# wagband_chestpiece_pre_route.net
KiCad netlist of a schematic drawn in EAGLE
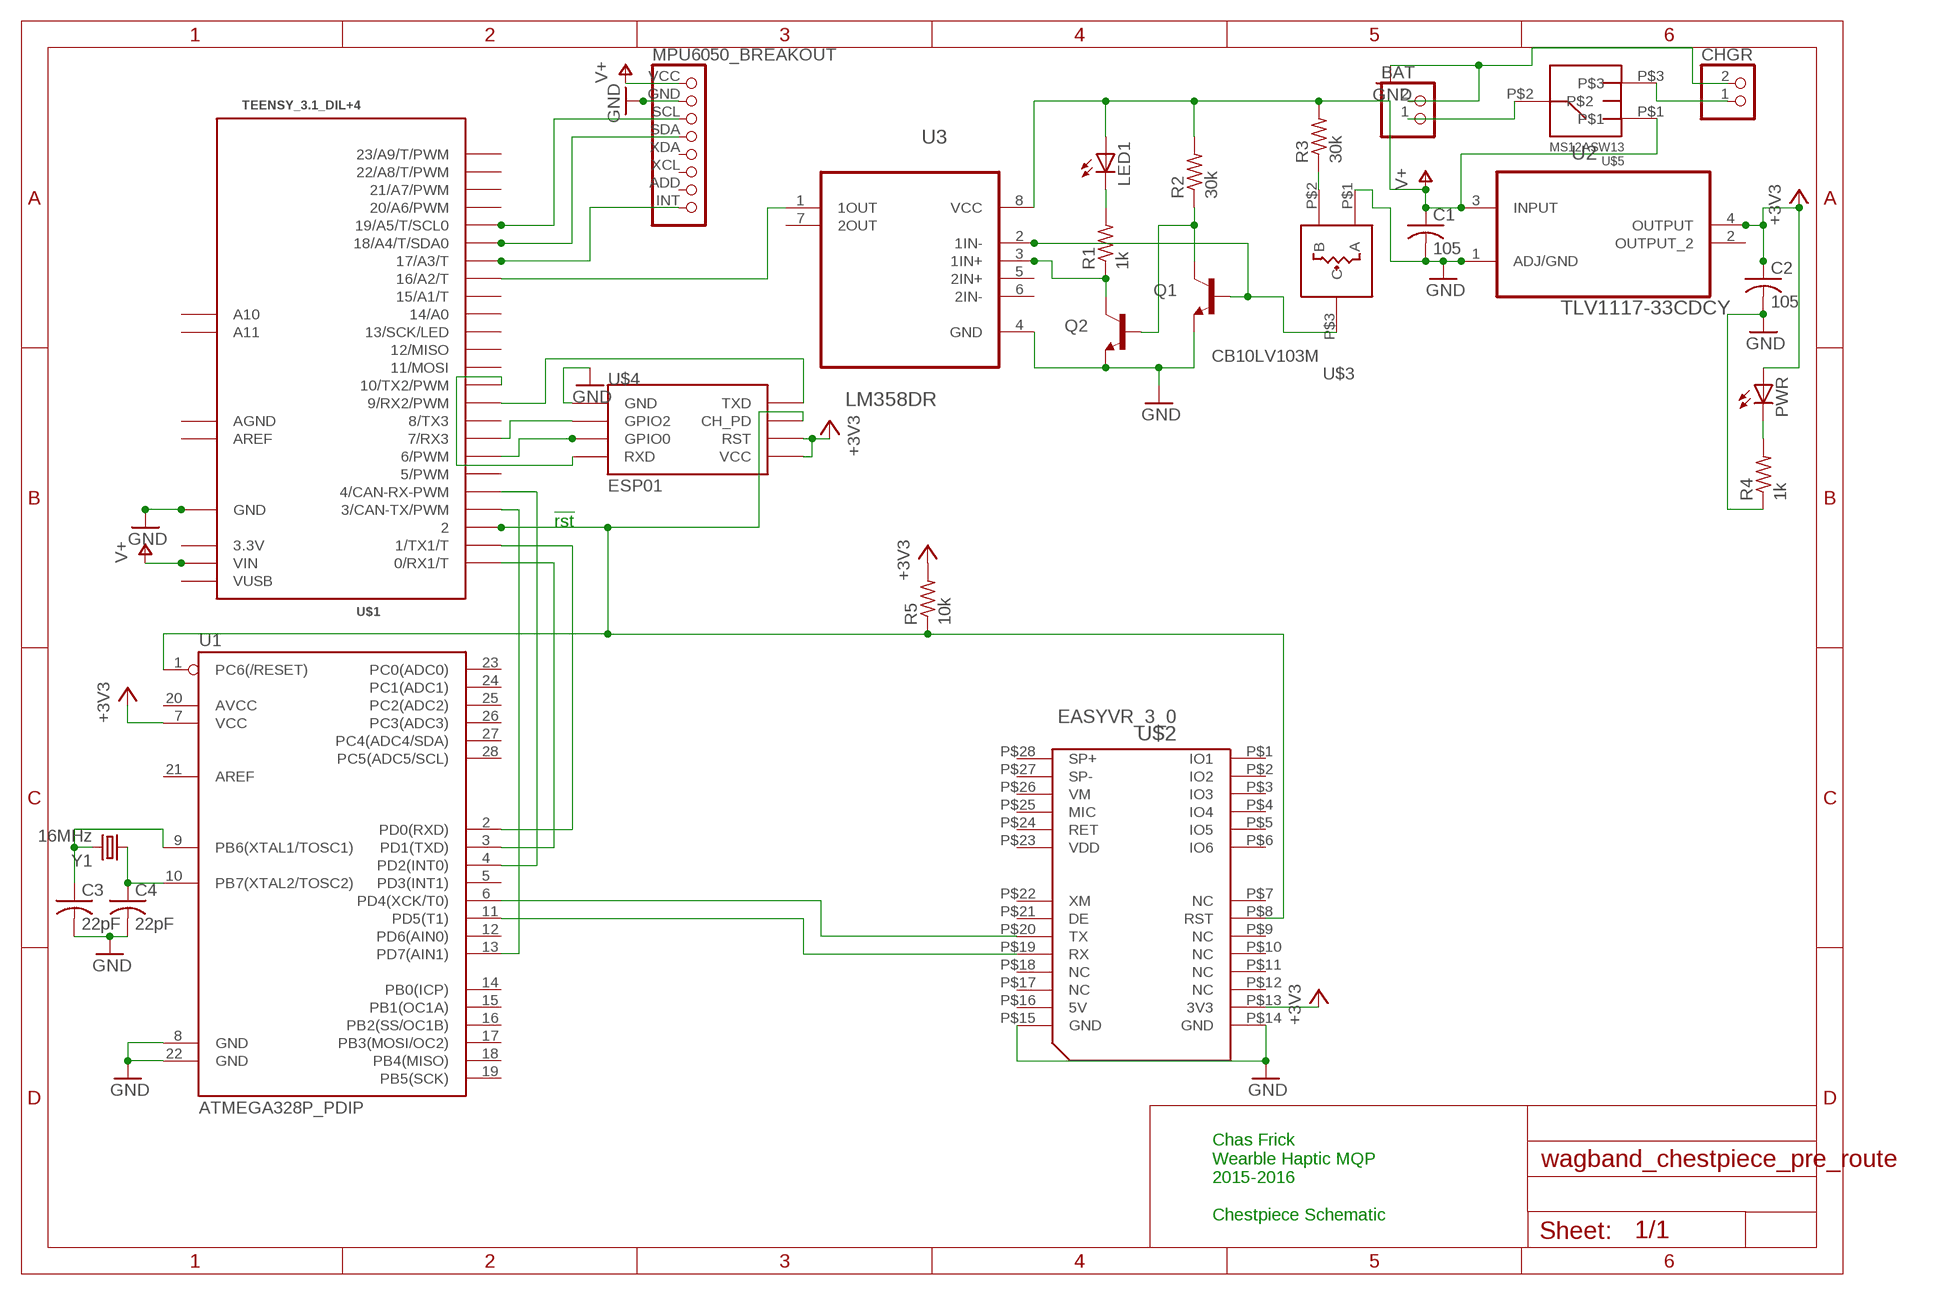
[diagram p0: schematic, sheet 1]

(export (version "E")
  (design (tool "Eeschema 10.0.6"))
  (components
    (comp (ref "BAT")
      (value "JST_2PIN-THM-RA")
      (footprint "eagle-import:JST-PH-2-THM-RA")
      (libsource (lib "eagle-import") (part "JST_2PIN-THM-RA"))
    )
    (comp (ref "C1")
      (value "105")
      (footprint "eagle-import:C0805K")
      (libsource (lib "eagle-import") (part "resistor_C-USC0805K"))
    )
    (comp (ref "C2")
      (value "105")
      (footprint "eagle-import:C0805K")
      (libsource (lib "eagle-import") (part "resistor_C-USC0805K"))
    )
    (comp (ref "C3")
      (value "22pF")
      (footprint "eagle-import:C1206K")
      (libsource (lib "eagle-import") (part "C-USC1206K"))
    )
    (comp (ref "C4")
      (value "22pF")
      (footprint "eagle-import:C1206K")
      (libsource (lib "eagle-import") (part "C-USC1206K"))
    )
    (comp (ref "CHGR")
      (value "JST_2PIN-THM-RA")
      (footprint "eagle-import:JST-PH-2-THM-RA")
      (libsource (lib "eagle-import") (part "JST_2PIN-THM-RA"))
    )
    (comp (ref "LED1")
      (value "LED5MM")
      (footprint "eagle-import:LED5MM")
      (libsource (lib "eagle-import") (part "LED5MM"))
    )
    (comp (ref "MPU6050_BREAKOUT")
      (value "MPU6050_BREAKOUT")
      (footprint "eagle-import:MPU6050")
      (libsource (lib "eagle-import") (part "MPU6050_BREAKOUT"))
    )
    (comp (ref "PWR")
      (value "LED5MM")
      (footprint "eagle-import:LED5MM")
      (libsource (lib "eagle-import") (part "LED5MM"))
    )
    (comp (ref "Q1")
      (value "TRANSISTOR_NPNMMBT3904")
      (footprint "eagle-import:SOT-23")
      (libsource (lib "eagle-import") (part "TRANSISTOR_NPNMMBT3904"))
    )
    (comp (ref "Q2")
      (value "TRANSISTOR_NPNMMBT3904")
      (footprint "eagle-import:SOT-23")
      (libsource (lib "eagle-import") (part "TRANSISTOR_NPNMMBT3904"))
    )
    (comp (ref "R1")
      (value "1k")
      (footprint "eagle-import:R1206")
      (libsource (lib "eagle-import") (part "R-US_R1206"))
    )
    (comp (ref "R2")
      (value "30k")
      (footprint "eagle-import:R1206")
      (libsource (lib "eagle-import") (part "R-US_R1206"))
    )
    (comp (ref "R3")
      (value "30k")
      (footprint "eagle-import:R1206")
      (libsource (lib "eagle-import") (part "R-US_R1206"))
    )
    (comp (ref "R4")
      (value "1k")
      (footprint "eagle-import:R1206")
      (libsource (lib "eagle-import") (part "R-US_R1206"))
    )
    (comp (ref "R5")
      (value "10k")
      (footprint "eagle-import:R1206")
      (libsource (lib "eagle-import") (part "R-US_R1206"))
    )
    (comp (ref "U$1")
      (value "TEENSY_3.1_DIL+4")
      (footprint "eagle-import:TEENSY3-DIL+4")
      (libsource (lib "eagle-import") (part "TEENSY_3.1_DIL+4"))
    )
    (comp (ref "U$2")
      (value "EASYVR_3_0")
      (footprint "eagle-import:EASYVR_3_0")
      (libsource (lib "eagle-import") (part "EASYVR_3_0"))
    )
    (comp (ref "U$3")
      (value "CB10LV103M")
      (footprint "eagle-import:CB10")
      (libsource (lib "eagle-import") (part "CB10LV103M"))
    )
    (comp (ref "U$4")
      (value "ESP01")
      (footprint "eagle-import:ESP01")
      (libsource (lib "eagle-import") (part "ESP01"))
    )
    (comp (ref "U$5")
      (value "MS12ASW13")
      (footprint "eagle-import:SPDT")
      (libsource (lib "eagle-import") (part "MS12ASW13"))
    )
    (comp (ref "U1")
      (value "ATMEGA328P_PDIP")
      (footprint "eagle-import:DIL28-3")
      (libsource (lib "eagle-import") (part "ATMEGA328P_PDIP"))
    )
    (comp (ref "U2")
      (value "TLV1117-33CDCY")
      (footprint "eagle-import:SOT230P700X180-4N")
      (libsource (lib "eagle-import") (part "TLV1117-33CDCY"))
    )
    (comp (ref "U3")
      (value "LM358DR")
      (footprint "eagle-import:SOIC127P600X175-8N")
      (libsource (lib "eagle-import") (part "LM358DR"))
    )
    (comp (ref "Y1")
      (value "16MHz")
      (footprint "eagle-import:HC49UP")
      (libsource (lib "eagle-import") (part "CRYSTALSMD"))
    )
  )
  (nets
    (net (code "1") (name "+3V3") (class "Default")
      (node (ref "C2") (pin "1") (pinfunction "1_1") (pintype "passive"))
      (node (ref "PWR") (pin "A") (pinfunction "A_A") (pintype "passive"))
      (node (ref "R5") (pin "2") (pinfunction "2_2") (pintype "passive"))
      (node (ref "U$2") (pin "P$13") (pinfunction "3V3_P$13") (pintype "power_in"))
      (node (ref "U$4") (pin "RST") (pinfunction "RST_RST") (pintype "bidirectional"))
      (node (ref "U$4") (pin "VCC") (pinfunction "VCC_VCC") (pintype "bidirectional"))
      (node (ref "U1") (pin "7") (pinfunction "VCC_7") (pintype "bidirectional"))
      (node (ref "U2") (pin "4") (pinfunction "OUTPUT_4") (pintype "output"))
    )
    (net (code "2") (name "/3.3V") (class "Default")
      (node (ref "U$1") (pin "3.3V") (pinfunction "3.3V_3.3V") (pintype "power_in"))
    )
    (net (code "3") (name "/5V") (class "Default")
      (node (ref "U$2") (pin "P$16") (pinfunction "5V_P$16") (pintype "power_in"))
    )
    (net (code "4") (name "/AGND") (class "Default")
      (node (ref "U$1") (pin "AGND") (pinfunction "AGND_AGND") (pintype "power_in"))
    )
    (net (code "5") (name "/AREF") (class "Default")
      (node (ref "U$1") (pin "AREF") (pinfunction "AREF_AREF") (pintype "power_in"))
    )
    (net (code "6") (name "/VDD") (class "Default")
      (node (ref "U$2") (pin "P$23") (pinfunction "VDD_P$23") (pintype "power_in"))
    )
    (net (code "7") (name "/VUSB") (class "Default")
      (node (ref "U$1") (pin "VUSB") (pinfunction "VUSB_VUSB") (pintype "power_in"))
    )
    (net (code "8") (name "GND") (class "Default")
      (node (ref "BAT") (pin "2") (pinfunction "1_2") (pintype "passive"))
      (node (ref "C1") (pin "2") (pinfunction "2_2") (pintype "passive"))
      (node (ref "C2") (pin "2") (pinfunction "2_2") (pintype "passive"))
      (node (ref "C3") (pin "2") (pinfunction "2_2") (pintype "passive"))
      (node (ref "C4") (pin "2") (pinfunction "2_2") (pintype "passive"))
      (node (ref "CHGR") (pin "2") (pinfunction "1_2") (pintype "passive"))
      (node (ref "MPU6050_BREAKOUT") (pin "GND") (pinfunction "GND_GND") (pintype "passive"))
      (node (ref "Q1") (pin "2") (pinfunction "E_2") (pintype "passive"))
      (node (ref "Q2") (pin "2") (pinfunction "E_2") (pintype "passive"))
      (node (ref "R4") (pin "1") (pinfunction "1_1") (pintype "passive"))
      (node (ref "U$1") (pin "GND") (pinfunction "GND_GND") (pintype "power_in"))
      (node (ref "U$2") (pin "P$14") (pinfunction "GND_P$14") (pintype "power_in"))
      (node (ref "U$2") (pin "P$15") (pinfunction "GND_P$15") (pintype "power_in"))
      (node (ref "U$3") (pin "P$1") (pinfunction "A_P$1") (pintype "bidirectional"))
      (node (ref "U$4") (pin "GND") (pinfunction "GND_GND") (pintype "bidirectional"))
      (node (ref "U1") (pin "22") (pinfunction "GND_22") (pintype "bidirectional"))
      (node (ref "U1") (pin "8") (pinfunction "GND_8") (pintype "bidirectional"))
      (node (ref "U2") (pin "1") (pinfunction "ADJ/GND_1") (pintype "input"))
      (node (ref "U3") (pin "4") (pinfunction "GND_4") (pintype "passive"))
    )
    (net (code "9") (name "Net-(BAT-2)") (class "Default")
      (node (ref "BAT") (pin "1") (pinfunction "2_1") (pintype "passive"))
      (node (ref "U$5") (pin "P$2") (pinfunction "P$2_P$2") (pintype "bidirectional"))
    )
    (net (code "10") (name "Net-(CHGR-2)") (class "Default")
      (node (ref "CHGR") (pin "1") (pinfunction "2_1") (pintype "passive"))
      (node (ref "U$5") (pin "P$3") (pinfunction "P$3_P$3") (pintype "bidirectional"))
    )
    (net (code "11") (name "Net-(LED1-C)") (class "Default")
      (node (ref "LED1") (pin "K") (pinfunction "C_K") (pintype "passive"))
      (node (ref "R1") (pin "2") (pinfunction "2_2") (pintype "passive"))
    )
    (net (code "12") (name "Net-(PWR-C)") (class "Default")
      (node (ref "PWR") (pin "K") (pinfunction "C_K") (pintype "passive"))
      (node (ref "R4") (pin "2") (pinfunction "2_2") (pintype "passive"))
    )
    (net (code "13") (name "Net-(Q1-B)") (class "Default")
      (node (ref "Q1") (pin "1") (pinfunction "B_1") (pintype "passive"))
      (node (ref "U$3") (pin "P$3") (pinfunction "C_P$3") (pintype "bidirectional"))
      (node (ref "U3") (pin "2") (pinfunction "1IN-_2") (pintype "input"))
    )
    (net (code "14") (name "Net-(Q1-C)") (class "Default")
      (node (ref "Q1") (pin "3") (pinfunction "C_3") (pintype "passive"))
      (node (ref "Q2") (pin "1") (pinfunction "B_1") (pintype "passive"))
      (node (ref "R2") (pin "1") (pinfunction "1_1") (pintype "passive"))
    )
    (net (code "15") (name "Net-(Q2-C)") (class "Default")
      (node (ref "Q2") (pin "3") (pinfunction "C_3") (pintype "passive"))
      (node (ref "R1") (pin "1") (pinfunction "1_1") (pintype "passive"))
      (node (ref "U3") (pin "3") (pinfunction "1IN+_3") (pintype "input"))
    )
    (net (code "16") (name "Net-(U$1-0{slash}RX1{slash}T)") (class "Default")
      (node (ref "U$1") (pin "0") (pinfunction "0/RX1/T_0") (pintype "bidirectional"))
      (node (ref "U1") (pin "3") (pinfunction "PD1(TXD)_3") (pintype "bidirectional"))
    )
    (net (code "17") (name "Net-(U$1-1{slash}TX1{slash}T)") (class "Default")
      (node (ref "U$1") (pin "1") (pinfunction "1/TX1/T_1") (pintype "bidirectional"))
      (node (ref "U1") (pin "2") (pinfunction "PD0(RXD)_2") (pintype "bidirectional"))
    )
    (net (code "18") (name "Net-(U$1-3{slash}CAN-TX{slash}PWM)") (class "Default")
      (node (ref "U$1") (pin "3") (pinfunction "3/CAN-TX/PWM_3") (pintype "bidirectional"))
      (node (ref "U1") (pin "13") (pinfunction "PD7(AIN1)_13") (pintype "bidirectional"))
    )
    (net (code "19") (name "Net-(U$1-4{slash}CAN-RX-PWM)") (class "Default")
      (node (ref "U$1") (pin "4") (pinfunction "4/CAN-RX-PWM_4") (pintype "bidirectional"))
      (node (ref "U1") (pin "4") (pinfunction "PD2(INT0)_4") (pintype "bidirectional"))
    )
    (net (code "20") (name "Net-(U$1-6{slash}PWM)") (class "Default")
      (node (ref "U$1") (pin "6") (pinfunction "6/PWM_6") (pintype "bidirectional"))
      (node (ref "U$4") (pin "GPIO0") (pinfunction "GPIO0_GPIO0") (pintype "bidirectional"))
    )
    (net (code "21") (name "Net-(U$1-7{slash}RX3)") (class "Default")
      (node (ref "U$1") (pin "7") (pinfunction "7/RX3_7") (pintype "bidirectional"))
      (node (ref "U$4") (pin "GPIO2") (pinfunction "GPIO2_GPIO2") (pintype "bidirectional"))
    )
    (net (code "22") (name "Net-(U$1-9{slash}RX2{slash}PWM)") (class "Default")
      (node (ref "U$1") (pin "9") (pinfunction "9/RX2/PWM_9") (pintype "bidirectional"))
      (node (ref "U$4") (pin "TX") (pinfunction "TXD_TX") (pintype "bidirectional"))
    )
    (net (code "23") (name "Net-(U$1-10{slash}TX2{slash}PWM)") (class "Default")
      (node (ref "U$1") (pin "10") (pinfunction "10/TX2/PWM_10") (pintype "bidirectional"))
      (node (ref "U$4") (pin "RX") (pinfunction "RXD_RX") (pintype "bidirectional"))
    )
    (net (code "24") (name "Net-(U$1-16{slash}A2{slash}T)") (class "Default")
      (node (ref "U$1") (pin "16/A2") (pinfunction "16/A2/T_16/A2") (pintype "bidirectional"))
      (node (ref "U3") (pin "1") (pinfunction "1OUT_1") (pintype "output"))
    )
    (net (code "25") (name "Net-(U$1-17{slash}A3{slash}T)") (class "Default")
      (node (ref "MPU6050_BREAKOUT") (pin "INT") (pinfunction "INT_INT") (pintype "passive"))
      (node (ref "U$1") (pin "17/A3") (pinfunction "17/A3/T_17/A3") (pintype "bidirectional"))
    )
    (net (code "26") (name "Net-(U$1-18{slash}A4{slash}T{slash}SDA0)") (class "Default")
      (node (ref "MPU6050_BREAKOUT") (pin "SDA") (pinfunction "SDA_SDA") (pintype "passive"))
      (node (ref "U$1") (pin "18/A4") (pinfunction "18/A4/T/SDA0_18/A4") (pintype "bidirectional"))
    )
    (net (code "27") (name "Net-(U$1-19{slash}A5{slash}T{slash}SCL0)") (class "Default")
      (node (ref "MPU6050_BREAKOUT") (pin "SCL") (pinfunction "SCL_SCL") (pintype "passive"))
      (node (ref "U$1") (pin "19/A5") (pinfunction "19/A5/T/SCL0_19/A5") (pintype "bidirectional"))
    )
    (net (code "28") (name "Net-(U$2-RST)") (class "Default")
      (node (ref "R5") (pin "1") (pinfunction "1_1") (pintype "passive"))
      (node (ref "U$1") (pin "2") (pinfunction "2_2") (pintype "bidirectional"))
      (node (ref "U$2") (pin "P$8") (pinfunction "RST_P$8") (pintype "input"))
      (node (ref "U$4") (pin "CH_PD") (pinfunction "CH_PD_CH_PD") (pintype "bidirectional"))
      (node (ref "U1") (pin "1") (pinfunction "PC6(/RESET)_1") (pintype "bidirectional"))
    )
    (net (code "29") (name "Net-(U$2-RX)") (class "Default")
      (node (ref "U$2") (pin "P$19") (pinfunction "RX_P$19") (pintype "input"))
      (node (ref "U1") (pin "11") (pinfunction "PD5(T1)_11") (pintype "bidirectional"))
    )
    (net (code "30") (name "Net-(U$2-TX)") (class "Default")
      (node (ref "U$2") (pin "P$20") (pinfunction "TX_P$20") (pintype "output"))
      (node (ref "U1") (pin "6") (pinfunction "PD4(XCK/T0)_6") (pintype "bidirectional"))
    )
    (net (code "31") (name "Net-(U$3-B)") (class "Default")
      (node (ref "R3") (pin "1") (pinfunction "1_1") (pintype "passive"))
      (node (ref "U$3") (pin "P$2") (pinfunction "B_P$2") (pintype "bidirectional"))
    )
    (net (code "32") (name "Net-(U1-PB6(XTAL1{slash}TOSC1))") (class "Default")
      (node (ref "C3") (pin "1") (pinfunction "1_1") (pintype "passive"))
      (node (ref "U1") (pin "9") (pinfunction "PB6(XTAL1/TOSC1)_9") (pintype "bidirectional"))
      (node (ref "Y1") (pin "2") (pinfunction "2_2") (pintype "passive"))
    )
    (net (code "33") (name "Net-(U1-PB7(XTAL2{slash}TOSC2))") (class "Default")
      (node (ref "C4") (pin "1") (pinfunction "1_1") (pintype "passive"))
      (node (ref "U1") (pin "10") (pinfunction "PB7(XTAL2/TOSC2)_10") (pintype "bidirectional"))
      (node (ref "Y1") (pin "1") (pinfunction "1_1") (pintype "passive"))
    )
    (net (code "34") (name "V+") (class "Default")
      (node (ref "C1") (pin "1") (pinfunction "1_1") (pintype "passive"))
      (node (ref "LED1") (pin "A") (pinfunction "A_A") (pintype "passive"))
      (node (ref "MPU6050_BREAKOUT") (pin "VCC") (pinfunction "VCC_VCC") (pintype "passive"))
      (node (ref "R2") (pin "2") (pinfunction "2_2") (pintype "passive"))
      (node (ref "R3") (pin "2") (pinfunction "2_2") (pintype "passive"))
      (node (ref "U$1") (pin "VIN") (pinfunction "VIN_VIN") (pintype "power_in"))
      (node (ref "U$5") (pin "P$1") (pinfunction "P$1_P$1") (pintype "bidirectional"))
      (node (ref "U2") (pin "3") (pinfunction "INPUT_3") (pintype "input"))
      (node (ref "U3") (pin "8") (pinfunction "VCC_8") (pintype "power_in"))
    )
    (net (code "35") (name "unconnected-(MPU6050_BREAKOUT-PadADD)") (class "Default")
      (node (ref "MPU6050_BREAKOUT") (pin "ADD") (pinfunction "ADD_ADD") (pintype "passive"))
    )
    (net (code "36") (name "unconnected-(MPU6050_BREAKOUT-PadXCL)") (class "Default")
      (node (ref "MPU6050_BREAKOUT") (pin "XCL") (pinfunction "XCL_XCL") (pintype "passive"))
    )
    (net (code "37") (name "unconnected-(MPU6050_BREAKOUT-PadXDA)") (class "Default")
      (node (ref "MPU6050_BREAKOUT") (pin "XDA") (pinfunction "XDA_XDA") (pintype "passive"))
    )
    (net (code "38") (name "unconnected-(U$1-5{slash}PWM-Pad5)") (class "Default")
      (node (ref "U$1") (pin "5") (pinfunction "5/PWM_5") (pintype "bidirectional"))
    )
    (net (code "39") (name "unconnected-(U$1-8{slash}TX3-Pad8)") (class "Default")
      (node (ref "U$1") (pin "8") (pinfunction "8/TX3_8") (pintype "bidirectional"))
    )
    (net (code "40") (name "unconnected-(U$1-11{slash}MOSI-Pad11)") (class "Default")
      (node (ref "U$1") (pin "11") (pinfunction "11/MOSI_11") (pintype "bidirectional"))
    )
    (net (code "41") (name "unconnected-(U$1-12{slash}MISO-Pad12)") (class "Default")
      (node (ref "U$1") (pin "12") (pinfunction "12/MISO_12") (pintype "bidirectional"))
    )
    (net (code "42") (name "unconnected-(U$1-13{slash}SCK{slash}LED-Pad13)") (class "Default")
      (node (ref "U$1") (pin "13") (pinfunction "13/SCK/LED_13") (pintype "bidirectional"))
    )
    (net (code "43") (name "unconnected-(U$1-15{slash}A1{slash}T-Pad15{slash}A1)") (class "Default")
      (node (ref "U$1") (pin "15/A1") (pinfunction "15/A1/T_15/A1") (pintype "bidirectional"))
    )
    (net (code "44") (name "unconnected-(U$1-20{slash}A6{slash}PWM-Pad20{slash}A6)") (class "Default")
      (node (ref "U$1") (pin "20/A6") (pinfunction "20/A6/PWM_20/A6") (pintype "bidirectional"))
    )
    (net (code "45") (name "unconnected-(U$1-21{slash}A7{slash}PWM-Pad21{slash}A7)") (class "Default")
      (node (ref "U$1") (pin "21/A7") (pinfunction "21/A7/PWM_21/A7") (pintype "bidirectional"))
    )
    (net (code "46") (name "unconnected-(U$1-22{slash}A8{slash}T{slash}PWM-Pad22{slash}A8)") (class "Default")
      (node (ref "U$1") (pin "22/A8") (pinfunction "22/A8/T/PWM_22/A8") (pintype "bidirectional"))
    )
    (net (code "47") (name "unconnected-(U$1-23{slash}A9{slash}T{slash}PWM-Pad23{slash}A9)") (class "Default")
      (node (ref "U$1") (pin "23/A9") (pinfunction "23/A9/T/PWM_23/A9") (pintype "bidirectional"))
    )
    (net (code "48") (name "unconnected-(U$1-Pad14{slash}A0)") (class "Default")
      (node (ref "U$1") (pin "14/A0") (pinfunction "14/A0_14/A0") (pintype "bidirectional"))
    )
    (net (code "49") (name "unconnected-(U$1-PadA10)") (class "Default")
      (node (ref "U$1") (pin "A10") (pinfunction "A10_A10") (pintype "bidirectional"))
    )
    (net (code "50") (name "unconnected-(U$1-PadA11)") (class "Default")
      (node (ref "U$1") (pin "A11") (pinfunction "A11_A11") (pintype "bidirectional"))
    )
    (net (code "51") (name "unconnected-(U$2-DE-PadP$21)") (class "Default")
      (node (ref "U$2") (pin "P$21") (pinfunction "DE_P$21") (pintype "bidirectional"))
    )
    (net (code "52") (name "unconnected-(U$2-IO1-PadP$1)") (class "Default")
      (node (ref "U$2") (pin "P$1") (pinfunction "IO1_P$1") (pintype "bidirectional"))
    )
    (net (code "53") (name "unconnected-(U$2-IO2-PadP$2)") (class "Default")
      (node (ref "U$2") (pin "P$2") (pinfunction "IO2_P$2") (pintype "bidirectional"))
    )
    (net (code "54") (name "unconnected-(U$2-IO3-PadP$3)") (class "Default")
      (node (ref "U$2") (pin "P$3") (pinfunction "IO3_P$3") (pintype "bidirectional"))
    )
    (net (code "55") (name "unconnected-(U$2-IO4-PadP$4)") (class "Default")
      (node (ref "U$2") (pin "P$4") (pinfunction "IO4_P$4") (pintype "bidirectional"))
    )
    (net (code "56") (name "unconnected-(U$2-IO5-PadP$5)") (class "Default")
      (node (ref "U$2") (pin "P$5") (pinfunction "IO5_P$5") (pintype "bidirectional"))
    )
    (net (code "57") (name "unconnected-(U$2-IO6-PadP$6)") (class "Default")
      (node (ref "U$2") (pin "P$6") (pinfunction "IO6_P$6") (pintype "bidirectional"))
    )
    (net (code "58") (name "unconnected-(U$2-MIC-PadP$25)") (class "Default")
      (node (ref "U$2") (pin "P$25") (pinfunction "MIC_P$25") (pintype "bidirectional"))
    )
    (net (code "59") (name "unconnected-(U$2-NC-PadP$7)") (class "Default")
      (node (ref "U$2") (pin "P$7") (pinfunction "NC_P$7") (pintype "no_connect"))
    )
    (net (code "60") (name "unconnected-(U$2-NC-PadP$9)") (class "Default")
      (node (ref "U$2") (pin "P$9") (pinfunction "NC_P$9") (pintype "no_connect"))
    )
    (net (code "61") (name "unconnected-(U$2-NC-PadP$10)") (class "Default")
      (node (ref "U$2") (pin "P$10") (pinfunction "NC_P$10") (pintype "no_connect"))
    )
    (net (code "62") (name "unconnected-(U$2-NC-PadP$11)") (class "Default")
      (node (ref "U$2") (pin "P$11") (pinfunction "NC_P$11") (pintype "no_connect"))
    )
    (net (code "63") (name "unconnected-(U$2-NC-PadP$12)") (class "Default")
      (node (ref "U$2") (pin "P$12") (pinfunction "NC_P$12") (pintype "no_connect"))
    )
    (net (code "64") (name "unconnected-(U$2-NC-PadP$17)") (class "Default")
      (node (ref "U$2") (pin "P$17") (pinfunction "NC_P$17") (pintype "no_connect"))
    )
    (net (code "65") (name "unconnected-(U$2-NC-PadP$18)") (class "Default")
      (node (ref "U$2") (pin "P$18") (pinfunction "NC_P$18") (pintype "no_connect"))
    )
    (net (code "66") (name "unconnected-(U$2-RET-PadP$24)") (class "Default")
      (node (ref "U$2") (pin "P$24") (pinfunction "RET_P$24") (pintype "bidirectional"))
    )
    (net (code "67") (name "unconnected-(U$2-SP+-PadP$28)") (class "Default")
      (node (ref "U$2") (pin "P$28") (pinfunction "SP+_P$28") (pintype "bidirectional"))
    )
    (net (code "68") (name "unconnected-(U$2-SP--PadP$27)") (class "Default")
      (node (ref "U$2") (pin "P$27") (pinfunction "SP-_P$27") (pintype "bidirectional"))
    )
    (net (code "69") (name "unconnected-(U$2-VM-PadP$26)") (class "Default")
      (node (ref "U$2") (pin "P$26") (pinfunction "VM_P$26") (pintype "bidirectional"))
    )
    (net (code "70") (name "unconnected-(U$2-XM-PadP$22)") (class "Default")
      (node (ref "U$2") (pin "P$22") (pinfunction "XM_P$22") (pintype "bidirectional"))
    )
    (net (code "71") (name "unconnected-(U1-AREF-Pad21)") (class "Default")
      (node (ref "U1") (pin "21") (pinfunction "AREF_21") (pintype "bidirectional"))
    )
    (net (code "72") (name "unconnected-(U1-AVCC-Pad20)") (class "Default")
      (node (ref "U1") (pin "20") (pinfunction "AVCC_20") (pintype "bidirectional"))
    )
    (net (code "73") (name "unconnected-(U1-PB0(ICP)-Pad14)") (class "Default")
      (node (ref "U1") (pin "14") (pinfunction "PB0(ICP)_14") (pintype "bidirectional"))
    )
    (net (code "74") (name "unconnected-(U1-PB1(OC1A)-Pad15)") (class "Default")
      (node (ref "U1") (pin "15") (pinfunction "PB1(OC1A)_15") (pintype "bidirectional"))
    )
    (net (code "75") (name "unconnected-(U1-PB2(SS{slash}OC1B)-Pad16)") (class "Default")
      (node (ref "U1") (pin "16") (pinfunction "PB2(SS/OC1B)_16") (pintype "bidirectional"))
    )
    (net (code "76") (name "unconnected-(U1-PB3(MOSI{slash}OC2)-Pad17)") (class "Default")
      (node (ref "U1") (pin "17") (pinfunction "PB3(MOSI/OC2)_17") (pintype "bidirectional"))
    )
    (net (code "77") (name "unconnected-(U1-PB4(MISO)-Pad18)") (class "Default")
      (node (ref "U1") (pin "18") (pinfunction "PB4(MISO)_18") (pintype "bidirectional"))
    )
    (net (code "78") (name "unconnected-(U1-PB5(SCK)-Pad19)") (class "Default")
      (node (ref "U1") (pin "19") (pinfunction "PB5(SCK)_19") (pintype "bidirectional"))
    )
    (net (code "79") (name "unconnected-(U1-PC0(ADC0)-Pad23)") (class "Default")
      (node (ref "U1") (pin "23") (pinfunction "PC0(ADC0)_23") (pintype "bidirectional"))
    )
    (net (code "80") (name "unconnected-(U1-PC1(ADC1)-Pad24)") (class "Default")
      (node (ref "U1") (pin "24") (pinfunction "PC1(ADC1)_24") (pintype "bidirectional"))
    )
    (net (code "81") (name "unconnected-(U1-PC2(ADC2)-Pad25)") (class "Default")
      (node (ref "U1") (pin "25") (pinfunction "PC2(ADC2)_25") (pintype "bidirectional"))
    )
    (net (code "82") (name "unconnected-(U1-PC3(ADC3)-Pad26)") (class "Default")
      (node (ref "U1") (pin "26") (pinfunction "PC3(ADC3)_26") (pintype "bidirectional"))
    )
    (net (code "83") (name "unconnected-(U1-PC4(ADC4{slash}SDA)-Pad27)") (class "Default")
      (node (ref "U1") (pin "27") (pinfunction "PC4(ADC4/SDA)_27") (pintype "bidirectional"))
    )
    (net (code "84") (name "unconnected-(U1-PC5(ADC5{slash}SCL)-Pad28)") (class "Default")
      (node (ref "U1") (pin "28") (pinfunction "PC5(ADC5/SCL)_28") (pintype "bidirectional"))
    )
    (net (code "85") (name "unconnected-(U1-PD3(INT1)-Pad5)") (class "Default")
      (node (ref "U1") (pin "5") (pinfunction "PD3(INT1)_5") (pintype "bidirectional"))
    )
    (net (code "86") (name "unconnected-(U1-PD6(AIN0)-Pad12)") (class "Default")
      (node (ref "U1") (pin "12") (pinfunction "PD6(AIN0)_12") (pintype "bidirectional"))
    )
    (net (code "87") (name "unconnected-(U2-OUTPUT_2-Pad2)") (class "Default")
      (node (ref "U2") (pin "2") (pinfunction "OUTPUT_2_2") (pintype "output"))
    )
    (net (code "88") (name "unconnected-(U3-2IN+-Pad5)") (class "Default")
      (node (ref "U3") (pin "5") (pinfunction "2IN+_5") (pintype "input"))
    )
    (net (code "89") (name "unconnected-(U3-2IN--Pad6)") (class "Default")
      (node (ref "U3") (pin "6") (pinfunction "2IN-_6") (pintype "input"))
    )
    (net (code "90") (name "unconnected-(U3-2OUT-Pad7)") (class "Default")
      (node (ref "U3") (pin "7") (pinfunction "2OUT_7") (pintype "output"))
    )
  )
)
